# ArduinoPWR-COMM-DIG_SDCard.net
KiCad netlist of a schematic drawn in Altium Designer
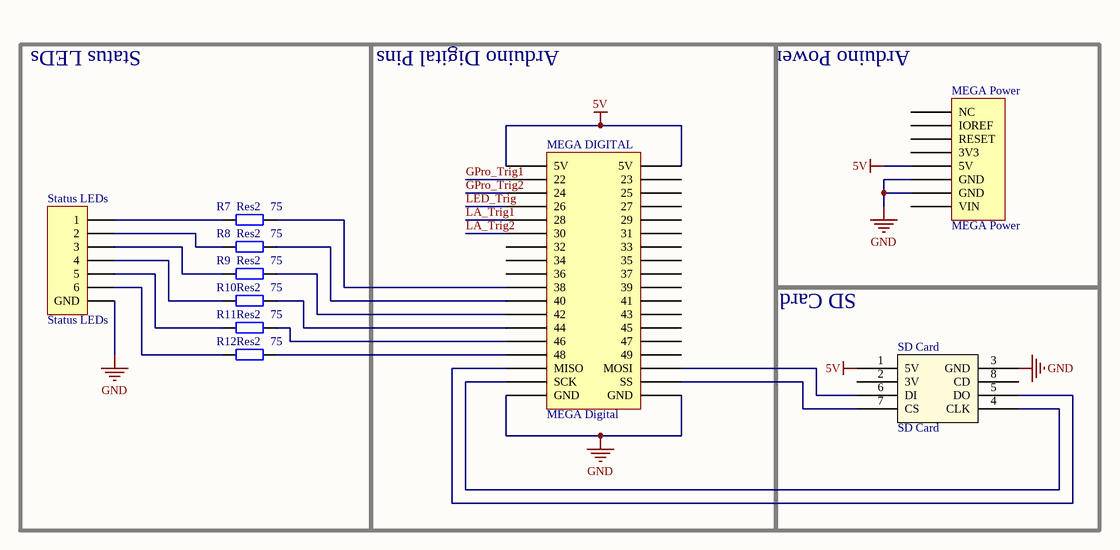
[diagram p0: ArduinoPWR-COMM-DIG_SDCard.SchDoc]

(export (version "E")
  (design (tool "Eeschema 10.0.6"))
  (components
    (comp (ref "MEGA DIGITAL")
      (value "MEGA Digital")
      (footprint "HDR2X18")
      (libsource (lib "Arduino2x18Header") (part "Component_1"))
    )
    (comp (ref "MEGA Power")
      (value "MEGA Power")
      (footprint "HDR1X8")
      (libsource (lib "Arduino8Header") (part "Component_1"))
    )
    (comp (ref "R7")
      (value "Res2")
      (footprint "AXIAL-0.4")
      (description "Resistor")
      (fields (field (name "ALTIUM_VALUE") "75") (field (name "PUBLISHER") "Altium Limited"))
      (libsource (lib "Miscellaneous Devices") (part "Res2"))
    )
    (comp (ref "R8")
      (value "Res2")
      (footprint "AXIAL-0.4")
      (description "Resistor")
      (fields (field (name "ALTIUM_VALUE") "75") (field (name "PUBLISHER") "Altium Limited"))
      (libsource (lib "Miscellaneous Devices") (part "Res2"))
    )
    (comp (ref "R9")
      (value "Res2")
      (footprint "AXIAL-0.4")
      (description "Resistor")
      (fields (field (name "ALTIUM_VALUE") "75") (field (name "PUBLISHER") "Altium Limited"))
      (libsource (lib "Miscellaneous Devices") (part "Res2"))
    )
    (comp (ref "R10")
      (value "Res2")
      (footprint "AXIAL-0.4")
      (description "Resistor")
      (fields (field (name "ALTIUM_VALUE") "75") (field (name "PUBLISHER") "Altium Limited"))
      (libsource (lib "Miscellaneous Devices") (part "Res2"))
    )
    (comp (ref "R11")
      (value "Res2")
      (footprint "AXIAL-0.4")
      (description "Resistor")
      (fields (field (name "ALTIUM_VALUE") "75") (field (name "PUBLISHER") "Altium Limited"))
      (libsource (lib "Miscellaneous Devices") (part "Res2"))
    )
    (comp (ref "R12")
      (value "Res2")
      (footprint "AXIAL-0.4")
      (description "Resistor")
      (fields (field (name "ALTIUM_VALUE") "75") (field (name "PUBLISHER") "Altium Limited"))
      (libsource (lib "Miscellaneous Devices") (part "Res2"))
    )
    (comp (ref "SD Card")
      (value "SD Card")
      (footprint "HDR1X8")
      (libsource (lib "AdafruitSDCard") (part "Component_1"))
    )
    (comp (ref "Status LEDs")
      (value "Status LEDs")
      (footprint "HDR1X7")
      (description "Header, 7-Pin")
      (fields (field (name "PUBLISHER") "Altium Limited"))
      (libsource (lib "Miscellaneous Connectors") (part "Header 7"))
    )
  )
  (nets
    (net (code "1") (name "/GPro_Trig1") (class "Default")
      (node (ref "MEGA DIGITAL") (pin "5") (pinfunction "22_5") (pintype "passive"))
    )
    (net (code "2") (name "/GPro_Trig2") (class "Default")
      (node (ref "MEGA DIGITAL") (pin "25") (pinfunction "24_25") (pintype "passive"))
    )
    (net (code "3") (name "/LA_Trig1") (class "Default")
      (node (ref "MEGA DIGITAL") (pin "9") (pinfunction "28_9") (pintype "passive"))
    )
    (net (code "4") (name "/LA_Trig2") (class "Default")
      (node (ref "MEGA DIGITAL") (pin "11") (pinfunction "30_11") (pintype "passive"))
    )
    (net (code "5") (name "/LED_Trig") (class "Default")
      (node (ref "MEGA DIGITAL") (pin "7") (pinfunction "26_7") (pintype "passive"))
    )
    (net (code "6") (name "5V") (class "Default")
      (node (ref "MEGA DIGITAL") (pin "1") (pinfunction "5V_1") (pintype "passive"))
      (node (ref "MEGA DIGITAL") (pin "2") (pinfunction "5V_2") (pintype "passive"))
      (node (ref "MEGA Power") (pin "5") (pinfunction "5V_5") (pintype "passive"))
      (node (ref "SD Card") (pin "1") (pinfunction "5V_1") (pintype "passive"))
    )
    (net (code "7") (name "GND") (class "Default")
      (node (ref "MEGA DIGITAL") (pin "35") (pinfunction "GND_35") (pintype "passive"))
      (node (ref "MEGA DIGITAL") (pin "36") (pinfunction "GND_36") (pintype "passive"))
      (node (ref "MEGA Power") (pin "6") (pinfunction "GND_6") (pintype "passive"))
      (node (ref "MEGA Power") (pin "7") (pinfunction "GND_7") (pintype "passive"))
      (node (ref "SD Card") (pin "3") (pinfunction "GND_3") (pintype "passive"))
      (node (ref "Status LEDs") (pin "7") (pinfunction "GND_7") (pintype "passive"))
    )
    (net (code "8") (name "Net-(MEGA DIGITAL-38)") (class "Default")
      (node (ref "MEGA DIGITAL") (pin "19") (pinfunction "38_19") (pintype "passive"))
      (node (ref "R7") (pin "1") (pinfunction "1_1") (pintype "passive"))
    )
    (net (code "9") (name "Net-(MEGA DIGITAL-40)") (class "Default")
      (node (ref "MEGA DIGITAL") (pin "21") (pinfunction "40_21") (pintype "passive"))
      (node (ref "R8") (pin "1") (pinfunction "1_1") (pintype "passive"))
    )
    (net (code "10") (name "Net-(MEGA DIGITAL-42)") (class "Default")
      (node (ref "MEGA DIGITAL") (pin "23") (pinfunction "42_23") (pintype "passive"))
      (node (ref "R9") (pin "1") (pinfunction "1_1") (pintype "passive"))
    )
    (net (code "11") (name "Net-(MEGA DIGITAL-44)") (class "Default")
      (node (ref "MEGA DIGITAL") (pin "3") (pinfunction "44_3") (pintype "passive"))
      (node (ref "R10") (pin "1") (pinfunction "1_1") (pintype "passive"))
    )
    (net (code "12") (name "Net-(MEGA DIGITAL-46)") (class "Default")
      (node (ref "MEGA DIGITAL") (pin "27") (pinfunction "46_27") (pintype "passive"))
      (node (ref "R11") (pin "1") (pinfunction "1_1") (pintype "passive"))
    )
    (net (code "13") (name "Net-(MEGA DIGITAL-48)") (class "Default")
      (node (ref "MEGA DIGITAL") (pin "29") (pinfunction "48_29") (pintype "passive"))
      (node (ref "R12") (pin "1") (pinfunction "1_1") (pintype "passive"))
    )
    (net (code "14") (name "Net-(MEGA DIGITAL-MISO)") (class "Default")
      (node (ref "MEGA DIGITAL") (pin "31") (pinfunction "MISO_31") (pintype "passive"))
      (node (ref "SD Card") (pin "5") (pinfunction "DO_5") (pintype "passive"))
    )
    (net (code "15") (name "Net-(MEGA DIGITAL-MOSI)") (class "Default")
      (node (ref "MEGA DIGITAL") (pin "32") (pinfunction "MOSI_32") (pintype "passive"))
      (node (ref "SD Card") (pin "6") (pinfunction "DI_6") (pintype "passive"))
    )
    (net (code "16") (name "Net-(MEGA DIGITAL-SCK)") (class "Default")
      (node (ref "MEGA DIGITAL") (pin "33") (pinfunction "SCK_33") (pintype "passive"))
      (node (ref "SD Card") (pin "4") (pinfunction "CLK_4") (pintype "passive"))
    )
    (net (code "17") (name "Net-(MEGA DIGITAL-SS)") (class "Default")
      (node (ref "MEGA DIGITAL") (pin "34") (pinfunction "SS_34") (pintype "passive"))
      (node (ref "SD Card") (pin "7") (pinfunction "CS_7") (pintype "passive"))
    )
    (net (code "18") (name "Net-(R7-Pad2)") (class "Default")
      (node (ref "R7") (pin "2") (pinfunction "2_2") (pintype "passive"))
      (node (ref "Status LEDs") (pin "1") (pinfunction "1_1") (pintype "passive"))
    )
    (net (code "19") (name "Net-(R8-Pad2)") (class "Default")
      (node (ref "R8") (pin "2") (pinfunction "2_2") (pintype "passive"))
      (node (ref "Status LEDs") (pin "2") (pinfunction "2_2") (pintype "passive"))
    )
    (net (code "20") (name "Net-(R9-Pad2)") (class "Default")
      (node (ref "R9") (pin "2") (pinfunction "2_2") (pintype "passive"))
      (node (ref "Status LEDs") (pin "3") (pinfunction "3_3") (pintype "passive"))
    )
    (net (code "21") (name "Net-(R10-Pad2)") (class "Default")
      (node (ref "R10") (pin "2") (pinfunction "2_2") (pintype "passive"))
      (node (ref "Status LEDs") (pin "4") (pinfunction "4_4") (pintype "passive"))
    )
    (net (code "22") (name "Net-(R11-Pad2)") (class "Default")
      (node (ref "R11") (pin "2") (pinfunction "2_2") (pintype "passive"))
      (node (ref "Status LEDs") (pin "5") (pinfunction "5_5") (pintype "passive"))
    )
    (net (code "23") (name "Net-(R12-Pad2)") (class "Default")
      (node (ref "R12") (pin "2") (pinfunction "2_2") (pintype "passive"))
      (node (ref "Status LEDs") (pin "6") (pinfunction "6_6") (pintype "passive"))
    )
    (net (code "24") (name "unconnected-(MEGA DIGITAL-23-Pad4)") (class "Default")
      (node (ref "MEGA DIGITAL") (pin "4") (pinfunction "23_4") (pintype "passive"))
    )
    (net (code "25") (name "unconnected-(MEGA DIGITAL-25-Pad6)") (class "Default")
      (node (ref "MEGA DIGITAL") (pin "6") (pinfunction "25_6") (pintype "passive"))
    )
    (net (code "26") (name "unconnected-(MEGA DIGITAL-27-Pad8)") (class "Default")
      (node (ref "MEGA DIGITAL") (pin "8") (pinfunction "27_8") (pintype "passive"))
    )
    (net (code "27") (name "unconnected-(MEGA DIGITAL-29-Pad10)") (class "Default")
      (node (ref "MEGA DIGITAL") (pin "10") (pinfunction "29_10") (pintype "passive"))
    )
    (net (code "28") (name "unconnected-(MEGA DIGITAL-31-Pad12)") (class "Default")
      (node (ref "MEGA DIGITAL") (pin "12") (pinfunction "31_12") (pintype "passive"))
    )
    (net (code "29") (name "unconnected-(MEGA DIGITAL-32-Pad13)") (class "Default")
      (node (ref "MEGA DIGITAL") (pin "13") (pinfunction "32_13") (pintype "passive"))
    )
    (net (code "30") (name "unconnected-(MEGA DIGITAL-33-Pad14)") (class "Default")
      (node (ref "MEGA DIGITAL") (pin "14") (pinfunction "33_14") (pintype "passive"))
    )
    (net (code "31") (name "unconnected-(MEGA DIGITAL-34-Pad15)") (class "Default")
      (node (ref "MEGA DIGITAL") (pin "15") (pinfunction "34_15") (pintype "passive"))
    )
    (net (code "32") (name "unconnected-(MEGA DIGITAL-35-Pad16)") (class "Default")
      (node (ref "MEGA DIGITAL") (pin "16") (pinfunction "35_16") (pintype "passive"))
    )
    (net (code "33") (name "unconnected-(MEGA DIGITAL-36-Pad17)") (class "Default")
      (node (ref "MEGA DIGITAL") (pin "17") (pinfunction "36_17") (pintype "passive"))
    )
    (net (code "34") (name "unconnected-(MEGA DIGITAL-37-Pad18)") (class "Default")
      (node (ref "MEGA DIGITAL") (pin "18") (pinfunction "37_18") (pintype "passive"))
    )
    (net (code "35") (name "unconnected-(MEGA DIGITAL-39-Pad20)") (class "Default")
      (node (ref "MEGA DIGITAL") (pin "20") (pinfunction "39_20") (pintype "passive"))
    )
    (net (code "36") (name "unconnected-(MEGA DIGITAL-41-Pad22)") (class "Default")
      (node (ref "MEGA DIGITAL") (pin "22") (pinfunction "41_22") (pintype "passive"))
    )
    (net (code "37") (name "unconnected-(MEGA DIGITAL-43-Pad24)") (class "Default")
      (node (ref "MEGA DIGITAL") (pin "24") (pinfunction "43_24") (pintype "passive"))
    )
    (net (code "38") (name "unconnected-(MEGA DIGITAL-45-Pad26)") (class "Default")
      (node (ref "MEGA DIGITAL") (pin "26") (pinfunction "45_26") (pintype "passive"))
    )
    (net (code "39") (name "unconnected-(MEGA DIGITAL-47-Pad28)") (class "Default")
      (node (ref "MEGA DIGITAL") (pin "28") (pinfunction "47_28") (pintype "passive"))
    )
    (net (code "40") (name "unconnected-(MEGA DIGITAL-49-Pad30)") (class "Default")
      (node (ref "MEGA DIGITAL") (pin "30") (pinfunction "49_30") (pintype "passive"))
    )
    (net (code "41") (name "unconnected-(MEGA Power-3V3-Pad4)") (class "Default")
      (node (ref "MEGA Power") (pin "4") (pinfunction "3V3_4") (pintype "passive"))
    )
    (net (code "42") (name "unconnected-(MEGA Power-IOREF-Pad2)") (class "Default")
      (node (ref "MEGA Power") (pin "2") (pinfunction "IOREF_2") (pintype "passive"))
    )
    (net (code "43") (name "unconnected-(MEGA Power-NC-Pad1)") (class "Default")
      (node (ref "MEGA Power") (pin "1") (pinfunction "NC_1") (pintype "passive"))
    )
    (net (code "44") (name "unconnected-(MEGA Power-RESET-Pad3)") (class "Default")
      (node (ref "MEGA Power") (pin "3") (pinfunction "RESET_3") (pintype "passive"))
    )
    (net (code "45") (name "unconnected-(MEGA Power-VIN-Pad8)") (class "Default")
      (node (ref "MEGA Power") (pin "8") (pinfunction "VIN_8") (pintype "passive"))
    )
    (net (code "46") (name "unconnected-(SD Card-3V-Pad2)") (class "Default")
      (node (ref "SD Card") (pin "2") (pinfunction "3V_2") (pintype "passive"))
    )
    (net (code "47") (name "unconnected-(SD Card-CD-Pad8)") (class "Default")
      (node (ref "SD Card") (pin "8") (pinfunction "CD_8") (pintype "passive"))
    )
  )
)
